# 4-20mA_Inputs__3-6.net
KiCad netlist of a schematic drawn in Altium Designer
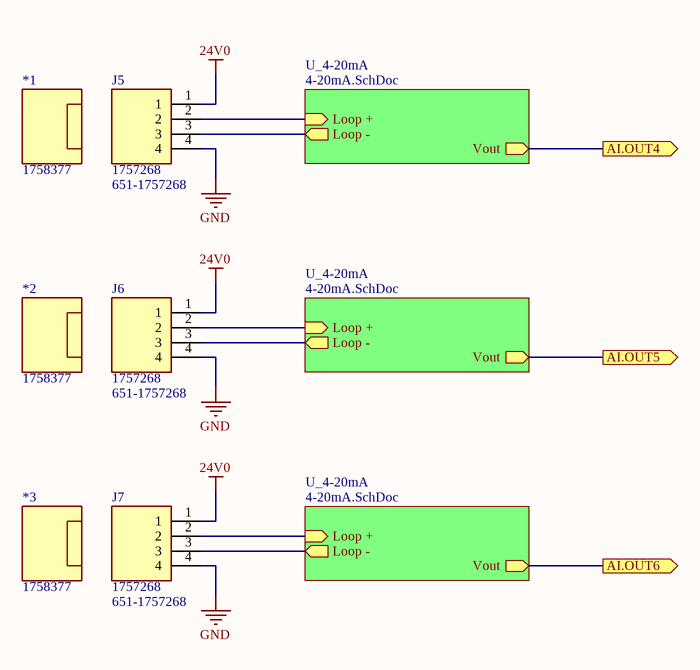
[diagram p0: 4-20mA_Inputs_(3-6).SchDoc]

(export (version "E")
  (design (tool "Eeschema 10.0.6"))
  (components
    (comp (ref "*1")
      (value "1758377")
      (footprint "Connector_1758377")
      (description "Plug, Terminal Block; 12 A; 250 V; 5.08 mm; 4 position, screw, Pre-Printed")
      (fields (field (name "MANUFACTURER") "Phoenix Contact") (field (name "VOLTAGE") "300V"))
      (libsource (lib "SamacSys") (part "1758377"))
    )
    (comp (ref "*2")
      (value "1758377")
      (footprint "Connector_1758377")
      (description "Plug, Terminal Block; 12 A; 250 V; 5.08 mm; 4 position, screw, Pre-Printed")
      (fields (field (name "MANUFACTURER") "Phoenix Contact") (field (name "VOLTAGE") "300V"))
      (libsource (lib "SamacSys") (part "1758377"))
    )
    (comp (ref "*3")
      (value "1758377")
      (footprint "Connector_1758377")
      (description "Plug, Terminal Block; 12 A; 250 V; 5.08 mm; 4 position, screw, Pre-Printed")
      (fields (field (name "MANUFACTURER") "Phoenix Contact") (field (name "VOLTAGE") "300V"))
      (libsource (lib "SamacSys") (part "1758377"))
    )
    (comp (ref "J5")
      (value "1757268")
      (footprint "SHDRRA4W103P0X508_1X4_2232X1200X875P")
      (description "Connector")
      (fields
        (field (name "MOUSER PART NUMBER") "651-1757268")
        (field (name "SUPPLIER PART NUMBER 1") "651-1757268")
      )
      (libsource (lib "SamacSys") (part "1757268"))
    )
    (comp (ref "J6")
      (value "1757268")
      (footprint "SHDRRA4W103P0X508_1X4_2232X1200X875P")
      (description "Connector")
      (fields
        (field (name "MOUSER PART NUMBER") "651-1757268")
        (field (name "SUPPLIER PART NUMBER 1") "651-1757268")
      )
      (libsource (lib "SamacSys") (part "1757268"))
    )
    (comp (ref "J7")
      (value "1757268")
      (footprint "SHDRRA4W103P0X508_1X4_2232X1200X875P")
      (description "Connector")
      (fields
        (field (name "MOUSER PART NUMBER") "651-1757268")
        (field (name "SUPPLIER PART NUMBER 1") "651-1757268")
      )
      (libsource (lib "SamacSys") (part "1757268"))
    )
  )
  (nets
    (net (code "4") (name "/Loop +") (class "Default")
      (node (ref "J5") (pin "2") (pinfunction "2_2") (pintype "passive"))
    )
    (net (code "5") (name "/Loop +_1") (class "Default")
      (node (ref "J7") (pin "2") (pinfunction "2_2") (pintype "passive"))
    )
    (net (code "6") (name "/Loop +_2") (class "Default")
      (node (ref "J6") (pin "2") (pinfunction "2_2") (pintype "passive"))
    )
    (net (code "7") (name "/Loop -") (class "Default")
      (node (ref "J5") (pin "3") (pinfunction "3_3") (pintype "passive"))
    )
    (net (code "8") (name "/Loop -_1") (class "Default")
      (node (ref "J7") (pin "3") (pinfunction "3_3") (pintype "passive"))
    )
    (net (code "9") (name "/Loop -_2") (class "Default")
      (node (ref "J6") (pin "3") (pinfunction "3_3") (pintype "passive"))
    )
    (net (code "10") (name "24V0") (class "Default")
      (node (ref "J5") (pin "1") (pinfunction "1_1") (pintype "passive"))
      (node (ref "J6") (pin "1") (pinfunction "1_1") (pintype "passive"))
      (node (ref "J7") (pin "1") (pinfunction "1_1") (pintype "passive"))
    )
    (net (code "11") (name "GND") (class "Default")
      (node (ref "J5") (pin "4") (pinfunction "4_4") (pintype "passive"))
      (node (ref "J6") (pin "4") (pinfunction "4_4") (pintype "passive"))
      (node (ref "J7") (pin "4") (pinfunction "4_4") (pintype "passive"))
    )
  )
)
